# TrueTouch.net
KiCad netlist of a schematic drawn in Altium Designer
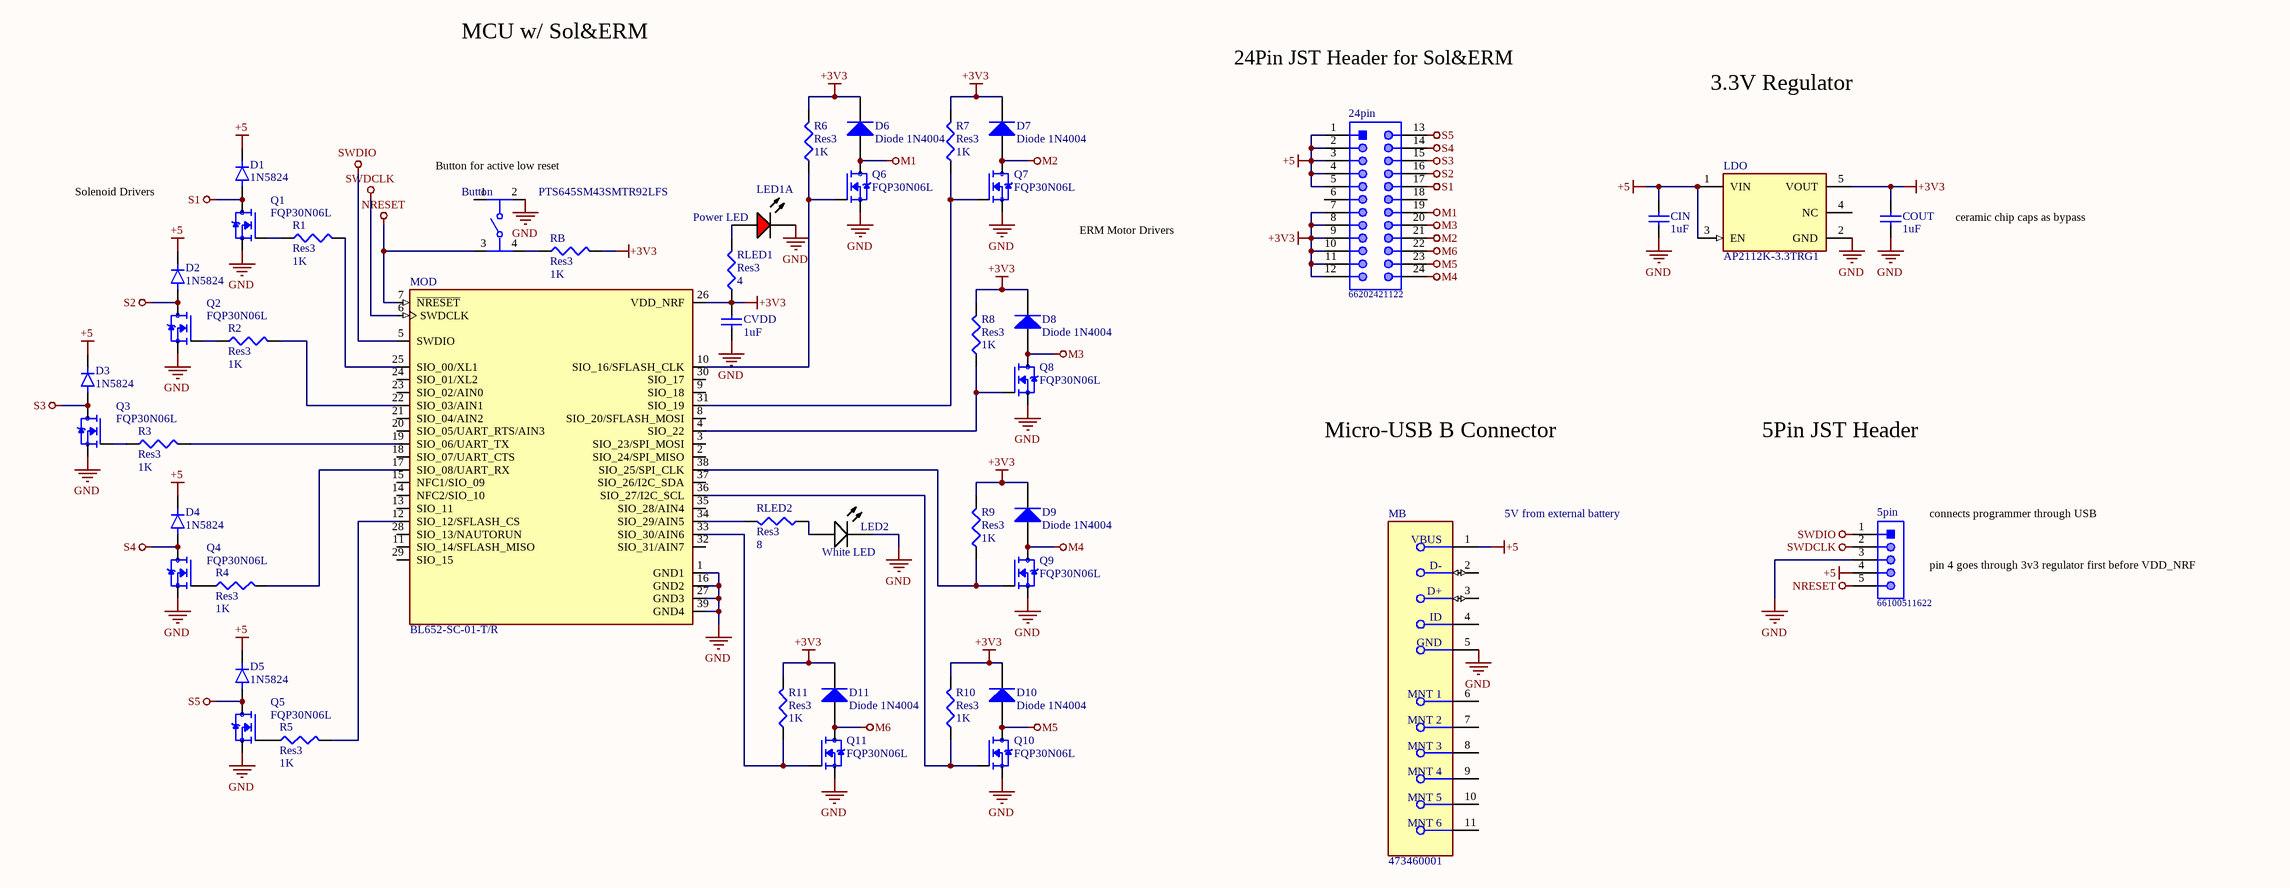
[diagram p0: TrueTouch.SchDoc]

(export (version "E")
  (design (tool "Eeschema 10.0.6"))
  (components
    (comp (ref "5pin")
      (value "66100511622")
      (footprint "66100511622")
      (description "Intercom Male Shrouded Locking Header WR-WTB, THT, Vertical, pitch 2.54 mm, 1 x 5 position")
      (fields (field (name "MANUFACTURER") "Wurth Elektronik") (field (name "PUBLISHER") "WurthElektronik"))
      (libsource (lib "Altium Content Vault") (part "WE-CN-1P-M-R5"))
    )
    (comp (ref "24pin")
      (value "66202421122")
      (footprint "66202421122")
      (description "THT Male Header WR-MPC3, Vertical, Dual Row, pitch 3 mm, 24 pins")
      (fields (field (name "MANUFACTURER") "Wurth Elektronik") (field (name "PUBLISHER") "WurthElektronik"))
      (libsource (lib "Altium Content Vault") (part "WE-CN-2P-M-R24_A"))
    )
    (comp (ref "Button")
      (value "PTS645SM43SMTR92LFS")
      (footprint "FP-PTS645SM43SMTR92LFS-MFG")
      (description "SWITCH TACTILE SPST-NO 0.05A 12V")
      (libsource (lib "Altium Content Vault") (part "1adf0dd01260c80cf25a44bfd6b99ba"))
    )
    (comp (ref "CIN")
      (value "1uF")
      (footprint "CAPC2013X140X45NL15T25")
      (fields (field (name "PART NUMBER") "GRM21BR71E105KA99L") (field (name "MANUFACTURER") "Murata"))
      (libsource (lib "Altium Content Vault") (part "CAP"))
    )
    (comp (ref "COUT")
      (value "1uF")
      (footprint "CAPC2013X140X45NL15T25")
      (fields (field (name "PART NUMBER") "GRM21BR71E105KA99L") (field (name "MANUFACTURER") "Murata"))
      (libsource (lib "Altium Content Vault") (part "CAP"))
    )
    (comp (ref "CVDD")
      (value "1uF")
      (footprint "CAPC2013X140X45NL15T25")
      (fields (field (name "PART NUMBER") "GRM21BR71E105KA99L") (field (name "MANUFACTURER") "Murata"))
      (libsource (lib "Altium Content Vault") (part "CAP"))
    )
    (comp (ref "D1")
      (value "1N5824")
      (footprint "DIOAD1898W129L762D1143")
      (description "Diode Schottky 30V 5A Through Hole Axial")
      (fields (field (name "MF") "Microsemi Corporation"))
      (libsource (lib "1N5824") (part "1N5824"))
    )
    (comp (ref "D2")
      (value "1N5824")
      (footprint "DIOAD1898W129L762D1143")
      (description "Diode Schottky 30V 5A Through Hole Axial")
      (fields (field (name "MF") "Microsemi Corporation"))
      (libsource (lib "1N5824") (part "1N5824"))
    )
    (comp (ref "D3")
      (value "1N5824")
      (footprint "DIOAD1898W129L762D1143")
      (description "Diode Schottky 30V 5A Through Hole Axial")
      (fields (field (name "MF") "Microsemi Corporation"))
      (libsource (lib "1N5824") (part "1N5824"))
    )
    (comp (ref "D4")
      (value "1N5824")
      (footprint "DIOAD1898W129L762D1143")
      (description "Diode Schottky 30V 5A Through Hole Axial")
      (fields (field (name "MF") "Microsemi Corporation"))
      (libsource (lib "1N5824") (part "1N5824"))
    )
    (comp (ref "D5")
      (value "1N5824")
      (footprint "DIOAD1898W129L762D1143")
      (description "Diode Schottky 30V 5A Through Hole Axial")
      (fields (field (name "MF") "Microsemi Corporation"))
      (libsource (lib "1N5824") (part "1N5824"))
    )
    (comp (ref "D6")
      (value "Diode 1N4004")
      (footprint "DO-41")
      (description "1 Amp General Purpose Rectifier")
      (fields (field (name "PUBLISHER") "Altium Limited"))
      (libsource (lib "Miscellaneous Devices") (part "Diode 1N4004"))
    )
    (comp (ref "D7")
      (value "Diode 1N4004")
      (footprint "DO-41")
      (description "1 Amp General Purpose Rectifier")
      (fields (field (name "PUBLISHER") "Altium Limited"))
      (libsource (lib "Miscellaneous Devices") (part "Diode 1N4004"))
    )
    (comp (ref "D8")
      (value "Diode 1N4004")
      (footprint "DO-41")
      (description "1 Amp General Purpose Rectifier")
      (fields (field (name "PUBLISHER") "Altium Limited"))
      (libsource (lib "Miscellaneous Devices") (part "Diode 1N4004"))
    )
    (comp (ref "D9")
      (value "Diode 1N4004")
      (footprint "DO-41")
      (description "1 Amp General Purpose Rectifier")
      (fields (field (name "PUBLISHER") "Altium Limited"))
      (libsource (lib "Miscellaneous Devices") (part "Diode 1N4004"))
    )
    (comp (ref "D10")
      (value "Diode 1N4004")
      (footprint "DO-41")
      (description "1 Amp General Purpose Rectifier")
      (fields (field (name "PUBLISHER") "Altium Limited"))
      (libsource (lib "Miscellaneous Devices") (part "Diode 1N4004"))
    )
    (comp (ref "D11")
      (value "Diode 1N4004")
      (footprint "DO-41")
      (description "1 Amp General Purpose Rectifier")
      (fields (field (name "PUBLISHER") "Altium Limited"))
      (libsource (lib "Miscellaneous Devices") (part "Diode 1N4004"))
    )
    (comp (ref "LDO")
      (value "AP2112K-3.3TRG1")
      (footprint "FP-SOT25-IPC_A")
      (description "IC REG LINEAR 3.3V 600MA SOT25")
      (libsource (lib "Altium Content Vault") (part "c8ab751aee5229183125ab046a11caa"))
    )
    (comp (ref "LED1")
      (value "Power LED")
      (footprint "CREE-XPEBRD-L1_V")
      (fields (field (name "MANUFACTURER") "Cree,Inc."))
      (libsource (lib "Altium Content Vault") (part "LED-RED-AKP-3"))
    )
    (comp (ref "LED2")
      (value "White LED")
      (footprint "LTST-LTW-C191TS5_V")
      (description "LED Uni-Color White, 70 mW, 20 mA, -20 to 80 degC, 2-Pin SMD, RoHS, Tape and Reel")
      (fields (field (name "TOLERANCE") "1%"))
      (libsource (lib "Altium Content Vault") (part "LED-WHITE-AK-2"))
    )
    (comp (ref "MB")
      (value "473460001")
      (footprint "FP-473460001-MFG")
      (description "CONN RCPT USB2.0 MICRO B SMD R/A")
      (fields
        (field (name "OCTOPART") "https://octopart.com/47346-0001-molex-7164928")
        (field (name "MANUFACTURER") "Molex")
      )
      (libsource (lib "Altium Content Vault") (part "53ae1f1d9b557310b43ca686e5bb76a"))
    )
    (comp (ref "MOD")
      (value "BL652-SC-01-T/R")
      (footprint "XCVR_BL652-SC-01-T/R")
      (description "Bluetooth Bluetooth v5.0 Transceiver Module 2.4GHz Antenna Not Included, I-PEX MHF4 Surface Mount")
      (fields (field (name "DIGI-KEY_PART_NUMBER") "BL652-SC-01-CT-ND") (field (name "MF") "Laird -"))
      (libsource (lib "BL652-SC-01-T_R") (part "BL652-SC-01-T/R"))
    )
    (comp (ref "Q1")
      (value "FQP30N06L")
      (footprint "TO220V")
      (description "N-Channel 60V 32A _Tc_ 79W _Tc_ Through Hole TO-220-3")
      (fields (field (name "MF") "ON Semiconductor"))
      (libsource (lib "FQP30N06L") (part "FQP30N06L"))
    )
    (comp (ref "Q2")
      (value "FQP30N06L")
      (footprint "TO220V")
      (description "N-Channel 60V 32A _Tc_ 79W _Tc_ Through Hole TO-220-3")
      (fields (field (name "MF") "ON Semiconductor"))
      (libsource (lib "FQP30N06L") (part "FQP30N06L"))
    )
    (comp (ref "Q3")
      (value "FQP30N06L")
      (footprint "TO220V")
      (description "N-Channel 60V 32A _Tc_ 79W _Tc_ Through Hole TO-220-3")
      (fields (field (name "MF") "ON Semiconductor"))
      (libsource (lib "FQP30N06L") (part "FQP30N06L"))
    )
    (comp (ref "Q4")
      (value "FQP30N06L")
      (footprint "TO220V")
      (description "N-Channel 60V 32A _Tc_ 79W _Tc_ Through Hole TO-220-3")
      (fields (field (name "MF") "ON Semiconductor"))
      (libsource (lib "FQP30N06L") (part "FQP30N06L"))
    )
    (comp (ref "Q5")
      (value "FQP30N06L")
      (footprint "TO220V")
      (description "N-Channel 60V 32A _Tc_ 79W _Tc_ Through Hole TO-220-3")
      (fields (field (name "MF") "ON Semiconductor"))
      (libsource (lib "FQP30N06L") (part "FQP30N06L"))
    )
    (comp (ref "Q6")
      (value "FQP30N06L")
      (footprint "TO220V")
      (description "N-Channel 60V 32A _Tc_ 79W _Tc_ Through Hole TO-220-3")
      (fields (field (name "MF") "ON Semiconductor"))
      (libsource (lib "FQP30N06L") (part "FQP30N06L"))
    )
    (comp (ref "Q7")
      (value "FQP30N06L")
      (footprint "TO220V")
      (description "N-Channel 60V 32A _Tc_ 79W _Tc_ Through Hole TO-220-3")
      (fields (field (name "MF") "ON Semiconductor"))
      (libsource (lib "FQP30N06L") (part "FQP30N06L"))
    )
    (comp (ref "Q8")
      (value "FQP30N06L")
      (footprint "TO220V")
      (description "N-Channel 60V 32A _Tc_ 79W _Tc_ Through Hole TO-220-3")
      (fields (field (name "MF") "ON Semiconductor"))
      (libsource (lib "FQP30N06L") (part "FQP30N06L"))
    )
    (comp (ref "Q9")
      (value "FQP30N06L")
      (footprint "TO220V")
      (description "N-Channel 60V 32A _Tc_ 79W _Tc_ Through Hole TO-220-3")
      (fields (field (name "MF") "ON Semiconductor"))
      (libsource (lib "FQP30N06L") (part "FQP30N06L"))
    )
    (comp (ref "Q10")
      (value "FQP30N06L")
      (footprint "TO220V")
      (description "N-Channel 60V 32A _Tc_ 79W _Tc_ Through Hole TO-220-3")
      (fields (field (name "MF") "ON Semiconductor"))
      (libsource (lib "FQP30N06L") (part "FQP30N06L"))
    )
    (comp (ref "Q11")
      (value "FQP30N06L")
      (footprint "TO220V")
      (description "N-Channel 60V 32A _Tc_ 79W _Tc_ Through Hole TO-220-3")
      (fields (field (name "MF") "ON Semiconductor"))
      (libsource (lib "FQP30N06L") (part "FQP30N06L"))
    )
    (comp (ref "R1")
      (value "Res3")
      (footprint "J1-0603")
      (description "Resistor")
      (fields (field (name "ALTIUM_VALUE") "1K") (field (name "PUBLISHER") "Altium Limited"))
      (libsource (lib "Miscellaneous Devices") (part "Res3"))
    )
    (comp (ref "R2")
      (value "Res3")
      (footprint "J1-0603")
      (description "Resistor")
      (fields (field (name "ALTIUM_VALUE") "1K") (field (name "PUBLISHER") "Altium Limited"))
      (libsource (lib "Miscellaneous Devices") (part "Res3"))
    )
    (comp (ref "R3")
      (value "Res3")
      (footprint "J1-0603")
      (description "Resistor")
      (fields (field (name "ALTIUM_VALUE") "1K") (field (name "PUBLISHER") "Altium Limited"))
      (libsource (lib "Miscellaneous Devices") (part "Res3"))
    )
    (comp (ref "R4")
      (value "Res3")
      (footprint "J1-0603")
      (description "Resistor")
      (fields (field (name "ALTIUM_VALUE") "1K") (field (name "PUBLISHER") "Altium Limited"))
      (libsource (lib "Miscellaneous Devices") (part "Res3"))
    )
    (comp (ref "R5")
      (value "Res3")
      (footprint "J1-0603")
      (description "Resistor")
      (fields (field (name "ALTIUM_VALUE") "1K") (field (name "PUBLISHER") "Altium Limited"))
      (libsource (lib "Miscellaneous Devices") (part "Res3"))
    )
    (comp (ref "R6")
      (value "Res3")
      (footprint "J1-0603")
      (description "Resistor")
      (fields (field (name "ALTIUM_VALUE") "1K") (field (name "PUBLISHER") "Altium Limited"))
      (libsource (lib "Miscellaneous Devices") (part "Res3"))
    )
    (comp (ref "R7")
      (value "Res3")
      (footprint "J1-0603")
      (description "Resistor")
      (fields (field (name "ALTIUM_VALUE") "1K") (field (name "PUBLISHER") "Altium Limited"))
      (libsource (lib "Miscellaneous Devices") (part "Res3"))
    )
    (comp (ref "R8")
      (value "Res3")
      (footprint "J1-0603")
      (description "Resistor")
      (fields (field (name "ALTIUM_VALUE") "1K") (field (name "PUBLISHER") "Altium Limited"))
      (libsource (lib "Miscellaneous Devices") (part "Res3"))
    )
    (comp (ref "R9")
      (value "Res3")
      (footprint "J1-0603")
      (description "Resistor")
      (fields (field (name "ALTIUM_VALUE") "1K") (field (name "PUBLISHER") "Altium Limited"))
      (libsource (lib "Miscellaneous Devices") (part "Res3"))
    )
    (comp (ref "R10")
      (value "Res3")
      (footprint "J1-0603")
      (description "Resistor")
      (fields (field (name "ALTIUM_VALUE") "1K") (field (name "PUBLISHER") "Altium Limited"))
      (libsource (lib "Miscellaneous Devices") (part "Res3"))
    )
    (comp (ref "R11")
      (value "Res3")
      (footprint "J1-0603")
      (description "Resistor")
      (fields (field (name "ALTIUM_VALUE") "1K") (field (name "PUBLISHER") "Altium Limited"))
      (libsource (lib "Miscellaneous Devices") (part "Res3"))
    )
    (comp (ref "RB")
      (value "Res3")
      (footprint "J1-0603")
      (description "Resistor")
      (fields (field (name "ALTIUM_VALUE") "1K") (field (name "PUBLISHER") "Altium Limited"))
      (libsource (lib "Miscellaneous Devices") (part "Res3"))
    )
    (comp (ref "RLED1")
      (value "Res3")
      (footprint "J1-0603")
      (description "Resistor")
      (fields (field (name "ALTIUM_VALUE") "4") (field (name "PUBLISHER") "Altium Limited"))
      (libsource (lib "Miscellaneous Devices") (part "Res3"))
    )
    (comp (ref "RLED2")
      (value "Res3")
      (footprint "J1-0603")
      (description "Resistor")
      (fields (field (name "ALTIUM_VALUE") "8") (field (name "PUBLISHER") "Altium Limited"))
      (libsource (lib "Miscellaneous Devices") (part "Res3"))
    )
  )
  (nets
    (net (code "1") (name "+3V3") (class "Default")
      (node (ref "24pin") (pin "10") (pinfunction "10_10") (pintype "passive"))
      (node (ref "24pin") (pin "11") (pinfunction "11_11") (pintype "passive"))
      (node (ref "24pin") (pin "12") (pinfunction "12_12") (pintype "passive"))
      (node (ref "24pin") (pin "7") (pinfunction "7_7") (pintype "passive"))
      (node (ref "24pin") (pin "8") (pinfunction "8_8") (pintype "passive"))
      (node (ref "24pin") (pin "9") (pinfunction "9_9") (pintype "passive"))
      (node (ref "COUT") (pin "2") (pinfunction "2_2") (pintype "passive"))
      (node (ref "CVDD") (pin "2") (pinfunction "2_2") (pintype "passive"))
      (node (ref "D10") (pin "2") (pinfunction "K_2") (pintype "passive"))
      (node (ref "D11") (pin "2") (pinfunction "K_2") (pintype "passive"))
      (node (ref "D6") (pin "2") (pinfunction "K_2") (pintype "passive"))
      (node (ref "D7") (pin "2") (pinfunction "K_2") (pintype "passive"))
      (node (ref "D8") (pin "2") (pinfunction "K_2") (pintype "passive"))
      (node (ref "D9") (pin "2") (pinfunction "K_2") (pintype "passive"))
      (node (ref "LDO") (pin "5") (pinfunction "VOUT_5") (pintype "power_in"))
      (node (ref "MOD") (pin "26") (pinfunction "VDD_NRF_26") (pintype "power_in"))
      (node (ref "R10") (pin "2") (pinfunction "2_2") (pintype "passive"))
      (node (ref "R11") (pin "2") (pinfunction "2_2") (pintype "passive"))
      (node (ref "R6") (pin "2") (pinfunction "2_2") (pintype "passive"))
      (node (ref "R7") (pin "2") (pinfunction "2_2") (pintype "passive"))
      (node (ref "R8") (pin "2") (pinfunction "2_2") (pintype "passive"))
      (node (ref "R9") (pin "2") (pinfunction "2_2") (pintype "passive"))
      (node (ref "RB") (pin "2") (pinfunction "2_2") (pintype "passive"))
      (node (ref "RLED1") (pin "1") (pinfunction "1_1") (pintype "passive"))
    )
    (net (code "2") (name "+5") (class "Default")
      (node (ref "24pin") (pin "1") (pinfunction "1_1") (pintype "passive"))
      (node (ref "24pin") (pin "2") (pinfunction "2_2") (pintype "passive"))
      (node (ref "24pin") (pin "3") (pinfunction "3_3") (pintype "passive"))
      (node (ref "24pin") (pin "4") (pinfunction "4_4") (pintype "passive"))
      (node (ref "24pin") (pin "5") (pinfunction "5_5") (pintype "passive"))
      (node (ref "5pin") (pin "4") (pinfunction "4_4") (pintype "passive"))
      (node (ref "CIN") (pin "2") (pinfunction "2_2") (pintype "passive"))
      (node (ref "D1") (pin "C") (pinfunction "K_C") (pintype "passive"))
      (node (ref "D2") (pin "C") (pinfunction "K_C") (pintype "passive"))
      (node (ref "D3") (pin "C") (pinfunction "K_C") (pintype "passive"))
      (node (ref "D4") (pin "C") (pinfunction "K_C") (pintype "passive"))
      (node (ref "D5") (pin "C") (pinfunction "K_C") (pintype "passive"))
      (node (ref "LDO") (pin "1") (pinfunction "VIN_1") (pintype "power_in"))
      (node (ref "LDO") (pin "3") (pinfunction "EN_3") (pintype "input"))
      (node (ref "MB") (pin "1") (pinfunction "VBUS_1") (pintype "power_in"))
    )
    (net (code "3") (name "GND") (class "Default")
      (node (ref "5pin") (pin "3") (pinfunction "3_3") (pintype "passive"))
      (node (ref "Button") (pin "2") (pinfunction "2_2") (pintype "passive"))
      (node (ref "CIN") (pin "1") (pinfunction "1_1") (pintype "passive"))
      (node (ref "COUT") (pin "1") (pinfunction "1_1") (pintype "passive"))
      (node (ref "CVDD") (pin "1") (pinfunction "1_1") (pintype "passive"))
      (node (ref "LDO") (pin "2") (pinfunction "GND_2") (pintype "power_in"))
      (node (ref "LED1") (pin "2") (pinfunction "K_2") (pintype "passive"))
      (node (ref "LED2") (pin "2") (pinfunction "K_2") (pintype "passive"))
      (node (ref "MB") (pin "5") (pinfunction "GND_5") (pintype "power_in"))
      (node (ref "MOD") (pin "1") (pinfunction "GND1_1") (pintype "power_in"))
      (node (ref "MOD") (pin "16") (pinfunction "GND2_16") (pintype "power_in"))
      (node (ref "MOD") (pin "27") (pinfunction "GND3_27") (pintype "power_in"))
      (node (ref "MOD") (pin "39") (pinfunction "GND4_39") (pintype "power_in"))
      (node (ref "Q1") (pin "3") (pinfunction "S_3") (pintype "passive"))
      (node (ref "Q10") (pin "3") (pinfunction "S_3") (pintype "passive"))
      (node (ref "Q11") (pin "3") (pinfunction "S_3") (pintype "passive"))
      (node (ref "Q2") (pin "3") (pinfunction "S_3") (pintype "passive"))
      (node (ref "Q3") (pin "3") (pinfunction "S_3") (pintype "passive"))
      (node (ref "Q4") (pin "3") (pinfunction "S_3") (pintype "passive"))
      (node (ref "Q5") (pin "3") (pinfunction "S_3") (pintype "passive"))
      (node (ref "Q6") (pin "3") (pinfunction "S_3") (pintype "passive"))
      (node (ref "Q7") (pin "3") (pinfunction "S_3") (pintype "passive"))
      (node (ref "Q8") (pin "3") (pinfunction "S_3") (pintype "passive"))
      (node (ref "Q9") (pin "3") (pinfunction "S_3") (pintype "passive"))
    )
    (net (code "4") (name "M1") (class "Default")
      (node (ref "24pin") (pin "19") (pinfunction "19_19") (pintype "passive"))
      (node (ref "D6") (pin "1") (pinfunction "A_1") (pintype "passive"))
      (node (ref "Q6") (pin "2") (pinfunction "D_2") (pintype "passive"))
    )
    (net (code "5") (name "M2") (class "Default")
      (node (ref "24pin") (pin "21") (pinfunction "21_21") (pintype "passive"))
      (node (ref "D7") (pin "1") (pinfunction "A_1") (pintype "passive"))
      (node (ref "Q7") (pin "2") (pinfunction "D_2") (pintype "passive"))
    )
    (net (code "6") (name "M3") (class "Default")
      (node (ref "24pin") (pin "20") (pinfunction "20_20") (pintype "passive"))
      (node (ref "D8") (pin "1") (pinfunction "A_1") (pintype "passive"))
      (node (ref "Q8") (pin "2") (pinfunction "D_2") (pintype "passive"))
    )
    (net (code "7") (name "M4") (class "Default")
      (node (ref "24pin") (pin "24") (pinfunction "24_24") (pintype "passive"))
      (node (ref "D9") (pin "1") (pinfunction "A_1") (pintype "passive"))
      (node (ref "Q9") (pin "2") (pinfunction "D_2") (pintype "passive"))
    )
    (net (code "8") (name "M5") (class "Default")
      (node (ref "24pin") (pin "23") (pinfunction "23_23") (pintype "passive"))
      (node (ref "D10") (pin "1") (pinfunction "A_1") (pintype "passive"))
      (node (ref "Q10") (pin "2") (pinfunction "D_2") (pintype "passive"))
    )
    (net (code "9") (name "M6") (class "Default")
      (node (ref "24pin") (pin "22") (pinfunction "22_22") (pintype "passive"))
      (node (ref "D11") (pin "1") (pinfunction "A_1") (pintype "passive"))
      (node (ref "Q11") (pin "2") (pinfunction "D_2") (pintype "passive"))
    )
    (net (code "10") (name "NRESET") (class "Default")
      (node (ref "5pin") (pin "5") (pinfunction "5_5") (pintype "passive"))
      (node (ref "Button") (pin "3") (pinfunction "3_3") (pintype "passive"))
      (node (ref "MOD") (pin "7") (pinfunction "~{NRESET}_7") (pintype "input"))
    )
    (net (code "11") (name "Net-(Button-Pad4)") (class "Default")
      (node (ref "Button") (pin "4") (pinfunction "4_4") (pintype "passive"))
      (node (ref "RB") (pin "1") (pinfunction "1_1") (pintype "passive"))
    )
    (net (code "12") (name "Net-(LED1A-A)") (class "Default")
      (node (ref "LED1") (pin "1") (pinfunction "A_1") (pintype "passive"))
      (node (ref "RLED1") (pin "2") (pinfunction "2_2") (pintype "passive"))
    )
    (net (code "13") (name "Net-(LED2-A)") (class "Default")
      (node (ref "LED2") (pin "1") (pinfunction "A_1") (pintype "passive"))
      (node (ref "RLED2") (pin "1") (pinfunction "1_1") (pintype "passive"))
    )
    (net (code "14") (name "Net-(MOD-SIO_00{slash}XL1)") (class "Default")
      (node (ref "MOD") (pin "25") (pinfunction "SIO_00/XL1_25") (pintype "bidirectional"))
      (node (ref "R1") (pin "2") (pinfunction "2_2") (pintype "passive"))
    )
    (net (code "15") (name "Net-(MOD-SIO_03{slash}AIN1)") (class "Default")
      (node (ref "MOD") (pin "22") (pinfunction "SIO_03/AIN1_22") (pintype "bidirectional"))
      (node (ref "R2") (pin "2") (pinfunction "2_2") (pintype "passive"))
    )
    (net (code "16") (name "Net-(MOD-SIO_06{slash}UART_TX)") (class "Default")
      (node (ref "MOD") (pin "19") (pinfunction "SIO_06/UART_TX_19") (pintype "bidirectional"))
      (node (ref "R3") (pin "2") (pinfunction "2_2") (pintype "passive"))
    )
    (net (code "17") (name "Net-(MOD-SIO_08{slash}UART_RX)") (class "Default")
      (node (ref "MOD") (pin "17") (pinfunction "SIO_08/UART_RX_17") (pintype "bidirectional"))
      (node (ref "R4") (pin "2") (pinfunction "2_2") (pintype "passive"))
    )
    (net (code "18") (name "Net-(MOD-SIO_12{slash}SFLASH_CS)") (class "Default")
      (node (ref "MOD") (pin "12") (pinfunction "SIO_12/SFLASH_CS_12") (pintype "bidirectional"))
      (node (ref "R5") (pin "2") (pinfunction "2_2") (pintype "passive"))
    )
    (net (code "19") (name "Net-(MOD-SIO_16{slash}SFLASH_CLK)") (class "Default")
      (node (ref "MOD") (pin "10") (pinfunction "SIO_16/SFLASH_CLK_10") (pintype "bidirectional"))
      (node (ref "Q6") (pin "1") (pinfunction "G_1") (pintype "passive"))
      (node (ref "R6") (pin "1") (pinfunction "1_1") (pintype "passive"))
    )
    (net (code "20") (name "Net-(MOD-SIO_19)") (class "Default")
      (node (ref "MOD") (pin "31") (pinfunction "SIO_19_31") (pintype "bidirectional"))
      (node (ref "Q7") (pin "1") (pinfunction "G_1") (pintype "passive"))
      (node (ref "R7") (pin "1") (pinfunction "1_1") (pintype "passive"))
    )
    (net (code "21") (name "Net-(MOD-SIO_22)") (class "Default")
      (node (ref "MOD") (pin "4") (pinfunction "SIO_22_4") (pintype "bidirectional"))
      (node (ref "Q8") (pin "1") (pinfunction "G_1") (pintype "passive"))
      (node (ref "R8") (pin "1") (pinfunction "1_1") (pintype "passive"))
    )
    (net (code "22") (name "Net-(MOD-SIO_25{slash}SPI_CLK)") (class "Default")
      (node (ref "MOD") (pin "38") (pinfunction "SIO_25/SPI_CLK_38") (pintype "bidirectional"))
      (node (ref "Q9") (pin "1") (pinfunction "G_1") (pintype "passive"))
      (node (ref "R9") (pin "1") (pinfunction "1_1") (pintype "passive"))
    )
    (net (code "23") (name "Net-(MOD-SIO_27{slash}I2C_SCL)") (class "Default")
      (node (ref "MOD") (pin "36") (pinfunction "SIO_27/I2C_SCL_36") (pintype "bidirectional"))
      (node (ref "Q10") (pin "1") (pinfunction "G_1") (pintype "passive"))
      (node (ref "R10") (pin "1") (pinfunction "1_1") (pintype "passive"))
    )
    (net (code "24") (name "Net-(MOD-SIO_29{slash}AIN5)") (class "Default")
      (node (ref "MOD") (pin "34") (pinfunction "SIO_29/AIN5_34") (pintype "bidirectional"))
      (node (ref "RLED2") (pin "2") (pinfunction "2_2") (pintype "passive"))
    )
    (net (code "25") (name "Net-(MOD-SIO_30{slash}AIN6)") (class "Default")
      (node (ref "MOD") (pin "33") (pinfunction "SIO_30/AIN6_33") (pintype "bidirectional"))
      (node (ref "Q11") (pin "1") (pinfunction "G_1") (pintype "passive"))
      (node (ref "R11") (pin "1") (pinfunction "1_1") (pintype "passive"))
    )
    (net (code "26") (name "Net-(Q1-G)") (class "Default")
      (node (ref "Q1") (pin "1") (pinfunction "G_1") (pintype "passive"))
      (node (ref "R1") (pin "1") (pinfunction "1_1") (pintype "passive"))
    )
    (net (code "27") (name "Net-(Q2-G)") (class "Default")
      (node (ref "Q2") (pin "1") (pinfunction "G_1") (pintype "passive"))
      (node (ref "R2") (pin "1") (pinfunction "1_1") (pintype "passive"))
    )
    (net (code "28") (name "Net-(Q3-G)") (class "Default")
      (node (ref "Q3") (pin "1") (pinfunction "G_1") (pintype "passive"))
      (node (ref "R3") (pin "1") (pinfunction "1_1") (pintype "passive"))
    )
    (net (code "29") (name "Net-(Q4-G)") (class "Default")
      (node (ref "Q4") (pin "1") (pinfunction "G_1") (pintype "passive"))
      (node (ref "R4") (pin "1") (pinfunction "1_1") (pintype "passive"))
    )
    (net (code "30") (name "Net-(Q5-G)") (class "Default")
      (node (ref "Q5") (pin "1") (pinfunction "G_1") (pintype "passive"))
      (node (ref "R5") (pin "1") (pinfunction "1_1") (pintype "passive"))
    )
    (net (code "31") (name "S1") (class "Default")
      (node (ref "24pin") (pin "17") (pinfunction "17_17") (pintype "passive"))
      (node (ref "D1") (pin "A") (pinfunction "A_A") (pintype "passive"))
      (node (ref "Q1") (pin "2") (pinfunction "D_2") (pintype "passive"))
    )
    (net (code "32") (name "S2") (class "Default")
      (node (ref "24pin") (pin "16") (pinfunction "16_16") (pintype "passive"))
      (node (ref "D2") (pin "A") (pinfunction "A_A") (pintype "passive"))
      (node (ref "Q2") (pin "2") (pinfunction "D_2") (pintype "passive"))
    )
    (net (code "33") (name "S3") (class "Default")
      (node (ref "24pin") (pin "15") (pinfunction "15_15") (pintype "passive"))
      (node (ref "D3") (pin "A") (pinfunction "A_A") (pintype "passive"))
      (node (ref "Q3") (pin "2") (pinfunction "D_2") (pintype "passive"))
    )
    (net (code "34") (name "S4") (class "Default")
      (node (ref "24pin") (pin "14") (pinfunction "14_14") (pintype "passive"))
      (node (ref "D4") (pin "A") (pinfunction "A_A") (pintype "passive"))
      (node (ref "Q4") (pin "2") (pinfunction "D_2") (pintype "passive"))
    )
    (net (code "35") (name "S5") (class "Default")
      (node (ref "24pin") (pin "13") (pinfunction "13_13") (pintype "passive"))
      (node (ref "D5") (pin "A") (pinfunction "A_A") (pintype "passive"))
      (node (ref "Q5") (pin "2") (pinfunction "D_2") (pintype "passive"))
    )
    (net (code "36") (name "SWDCLK") (class "Default")
      (node (ref "5pin") (pin "2") (pinfunction "2_2") (pintype "passive"))
      (node (ref "MOD") (pin "6") (pinfunction "SWDCLK_6") (pintype "input"))
    )
    (net (code "37") (name "SWDIO") (class "Default")
      (node (ref "5pin") (pin "1") (pinfunction "1_1") (pintype "passive"))
      (node (ref "MOD") (pin "5") (pinfunction "SWDIO_5") (pintype "bidirectional"))
    )
    (net (code "38") (name "unconnected-(24pin-Pad6)") (class "Default")
      (node (ref "24pin") (pin "6") (pinfunction "6_6") (pintype "passive"))
    )
    (net (code "39") (name "unconnected-(24pin-Pad18)") (class "Default")
      (node (ref "24pin") (pin "18") (pinfunction "18_18") (pintype "passive"))
    )
    (net (code "40") (name "unconnected-(Button-Pad1)") (class "Default")
      (node (ref "Button") (pin "1") (pinfunction "1_1") (pintype "passive"))
    )
    (net (code "41") (name "unconnected-(LDO-NC-Pad4)") (class "Default")
      (node (ref "LDO") (pin "4") (pinfunction "NC_4") (pintype "passive"))
    )
    (net (code "42") (name "unconnected-(MB-D+-Pad3)") (class "Default")
      (node (ref "MB") (pin "3") (pinfunction "D+_3") (pintype "bidirectional"))
    )
    (net (code "43") (name "unconnected-(MB-D--Pad2)") (class "Default")
      (node (ref "MB") (pin "2") (pinfunction "D-_2") (pintype "bidirectional"))
    )
    (net (code "44") (name "unconnected-(MB-ID-Pad4)") (class "Default")
      (node (ref "MB") (pin "4") (pinfunction "ID_4") (pintype "passive"))
    )
    (net (code "45") (name "unconnected-(MB-MNT_1-Pad6)") (class "Default")
      (node (ref "MB") (pin "6") (pinfunction "MNT_1_6") (pintype "passive"))
    )
    (net (code "46") (name "unconnected-(MB-MNT_2-Pad7)") (class "Default")
      (node (ref "MB") (pin "7") (pinfunction "MNT_2_7") (pintype "passive"))
    )
    (net (code "47") (name "unconnected-(MB-MNT_3-Pad8)") (class "Default")
      (node (ref "MB") (pin "8") (pinfunction "MNT_3_8") (pintype "passive"))
    )
    (net (code "48") (name "unconnected-(MB-MNT_4-Pad9)") (class "Default")
      (node (ref "MB") (pin "9") (pinfunction "MNT_4_9") (pintype "passive"))
    )
    (net (code "49") (name "unconnected-(MB-MNT_5-Pad10)") (class "Default")
      (node (ref "MB") (pin "10") (pinfunction "MNT_5_10") (pintype "passive"))
    )
    (net (code "50") (name "unconnected-(MB-MNT_6-Pad11)") (class "Default")
      (node (ref "MB") (pin "11") (pinfunction "MNT_6_11") (pintype "passive"))
    )
    (net (code "51") (name "unconnected-(MOD-NFC1{slash}SIO_09-Pad15)") (class "Default")
      (node (ref "MOD") (pin "15") (pinfunction "NFC1/SIO_09_15") (pintype "bidirectional"))
    )
    (net (code "52") (name "unconnected-(MOD-NFC2{slash}SIO_10-Pad14)") (class "Default")
      (node (ref "MOD") (pin "14") (pinfunction "NFC2/SIO_10_14") (pintype "bidirectional"))
    )
    (net (code "53") (name "unconnected-(MOD-SIO_01{slash}XL2-Pad24)") (class "Default")
      (node (ref "MOD") (pin "24") (pinfunction "SIO_01/XL2_24") (pintype "bidirectional"))
    )
    (net (code "54") (name "unconnected-(MOD-SIO_02{slash}AIN0-Pad23)") (class "Default")
      (node (ref "MOD") (pin "23") (pinfunction "SIO_02/AIN0_23") (pintype "bidirectional"))
    )
    (net (code "55") (name "unconnected-(MOD-SIO_04{slash}AIN2-Pad21)") (class "Default")
      (node (ref "MOD") (pin "21") (pinfunction "SIO_04/AIN2_21") (pintype "bidirectional"))
    )
    (net (code "56") (name "unconnected-(MOD-SIO_05{slash}UART_RTS{slash}AIN3-Pad20)") (class "Default")
      (node (ref "MOD") (pin "20") (pinfunction "SIO_05/UART_RTS/AIN3_20") (pintype "bidirectional"))
    )
    (net (code "57") (name "unconnected-(MOD-SIO_07{slash}UART_CTS-Pad18)") (class "Default")
      (node (ref "MOD") (pin "18") (pinfunction "SIO_07/UART_CTS_18") (pintype "bidirectional"))
    )
    (net (code "58") (name "unconnected-(MOD-SIO_11-Pad13)") (class "Default")
      (node (ref "MOD") (pin "13") (pinfunction "SIO_11_13") (pintype "bidirectional"))
    )
    (net (code "59") (name "unconnected-(MOD-SIO_13{slash}NAUTORUN-Pad28)") (class "Default")
      (node (ref "MOD") (pin "28") (pinfunction "SIO_13/NAUTORUN_28") (pintype "bidirectional"))
    )
    (net (code "60") (name "unconnected-(MOD-SIO_14{slash}SFLASH_MISO-Pad11)") (class "Default")
      (node (ref "MOD") (pin "11") (pinfunction "SIO_14/SFLASH_MISO_11") (pintype "bidirectional"))
    )
    (net (code "61") (name "unconnected-(MOD-SIO_15-Pad29)") (class "Default")
      (node (ref "MOD") (pin "29") (pinfunction "SIO_15_29") (pintype "bidirectional"))
    )
    (net (code "62") (name "unconnected-(MOD-SIO_17-Pad30)") (class "Default")
      (node (ref "MOD") (pin "30") (pinfunction "SIO_17_30") (pintype "bidirectional"))
    )
    (net (code "63") (name "unconnected-(MOD-SIO_18-Pad9)") (class "Default")
      (node (ref "MOD") (pin "9") (pinfunction "SIO_18_9") (pintype "bidirectional"))
    )
    (net (code "64") (name "unconnected-(MOD-SIO_20{slash}SFLASH_MOSI-Pad8)") (class "Default")
      (node (ref "MOD") (pin "8") (pinfunction "SIO_20/SFLASH_MOSI_8") (pintype "bidirectional"))
    )
    (net (code "65") (name "unconnected-(MOD-SIO_23{slash}SPI_MOSI-Pad3)") (class "Default")
      (node (ref "MOD") (pin "3") (pinfunction "SIO_23/SPI_MOSI_3") (pintype "bidirectional"))
    )
    (net (code "66") (name "unconnected-(MOD-SIO_24{slash}SPI_MISO-Pad2)") (class "Default")
      (node (ref "MOD") (pin "2") (pinfunction "SIO_24/SPI_MISO_2") (pintype "bidirectional"))
    )
    (net (code "67") (name "unconnected-(MOD-SIO_26{slash}I2C_SDA-Pad37)") (class "Default")
      (node (ref "MOD") (pin "37") (pinfunction "SIO_26/I2C_SDA_37") (pintype "bidirectional"))
    )
    (net (code "68") (name "unconnected-(MOD-SIO_28{slash}AIN4-Pad35)") (class "Default")
      (node (ref "MOD") (pin "35") (pinfunction "SIO_28/AIN4_35") (pintype "bidirectional"))
    )
    (net (code "69") (name "unconnected-(MOD-SIO_31{slash}AIN7-Pad32)") (class "Default")
      (node (ref "MOD") (pin "32") (pinfunction "SIO_31/AIN7_32") (pintype "bidirectional"))
    )
  )
)
